# LP.net
KiCad netlist of a schematic drawn in Altium Designer
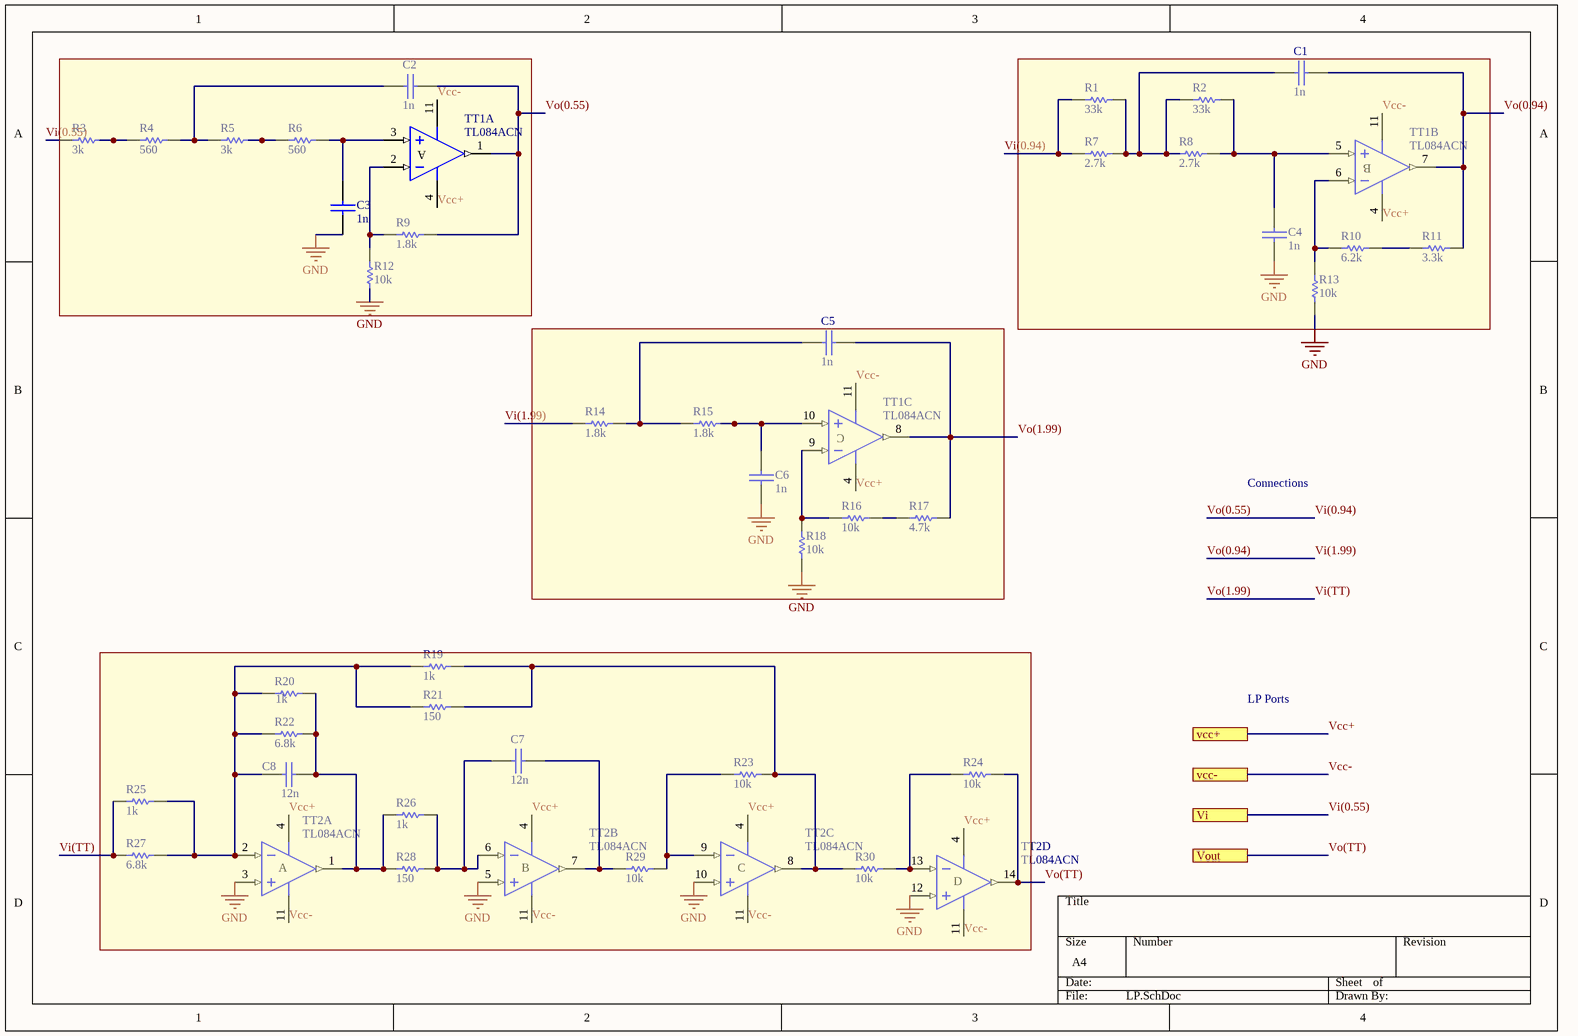
[diagram p0: LP.SchDoc]

(export (version "E")
  (design (tool "Eeschema 10.0.6"))
  (components
    (comp (ref "C1") (value "1n") (footprint "0805") (libsource (lib "LIBEBAL") (part "CAP")))
    (comp (ref "C2") (value "1n") (footprint "0805") (libsource (lib "LIBEBAL") (part "CAP")))
    (comp (ref "C3") (value "1n") (footprint "0805") (libsource (lib "LIBEBAL") (part "CAP")))
    (comp (ref "C4") (value "1n") (footprint "0805") (libsource (lib "LIBEBAL") (part "CAP")))
    (comp (ref "C5") (value "1n") (footprint "0805") (libsource (lib "LIBEBAL") (part "CAP")))
    (comp (ref "C6") (value "1n") (footprint "0805") (libsource (lib "LIBEBAL") (part "CAP")))
    (comp (ref "C7") (value "12n") (footprint "0805") (libsource (lib "LIBEBAL") (part "CAP")))
    (comp (ref "C8") (value "12n") (footprint "0805") (libsource (lib "LIBEBAL") (part "CAP")))
    (comp (ref "R1") (value "33k") (footprint "0805") (libsource (lib "LIBEBAL") (part "RES")))
    (comp (ref "R2") (value "33k") (footprint "0805") (libsource (lib "LIBEBAL") (part "RES")))
    (comp (ref "R3") (value "3k") (footprint "0805") (libsource (lib "LIBEBAL") (part "RES")))
    (comp (ref "R4") (value "560") (footprint "0805") (libsource (lib "LIBEBAL") (part "RES")))
    (comp (ref "R5") (value "3k") (footprint "0805") (libsource (lib "LIBEBAL") (part "RES")))
    (comp (ref "R6") (value "560") (footprint "0805") (libsource (lib "LIBEBAL") (part "RES")))
    (comp (ref "R7") (value "2.7k") (footprint "0805") (libsource (lib "LIBEBAL") (part "RES")))
    (comp (ref "R8") (value "2.7k") (footprint "0805") (libsource (lib "LIBEBAL") (part "RES")))
    (comp (ref "R9") (value "1.8k") (footprint "0805") (libsource (lib "LIBEBAL") (part "RES")))
    (comp (ref "R10") (value "6.2k") (footprint "0805") (libsource (lib "LIBEBAL") (part "RES")))
    (comp (ref "R11") (value "3.3k") (footprint "0805") (libsource (lib "LIBEBAL") (part "RES")))
    (comp (ref "R12") (value "10k") (footprint "0805") (libsource (lib "LIBEBAL") (part "RES")))
    (comp (ref "R13") (value "10k") (footprint "0805") (libsource (lib "LIBEBAL") (part "RES")))
    (comp (ref "R14") (value "1.8k") (footprint "0805") (libsource (lib "LIBEBAL") (part "RES")))
    (comp (ref "R15") (value "1.8k") (footprint "0805") (libsource (lib "LIBEBAL") (part "RES")))
    (comp (ref "R16") (value "10k") (footprint "0805") (libsource (lib "LIBEBAL") (part "RES")))
    (comp (ref "R17") (value "4.7k") (footprint "0805") (libsource (lib "LIBEBAL") (part "RES")))
    (comp (ref "R18") (value "10k") (footprint "0805") (libsource (lib "LIBEBAL") (part "RES")))
    (comp (ref "R19") (value "1k") (footprint "0805") (libsource (lib "LIBEBAL") (part "RES")))
    (comp (ref "R20") (value "1k") (footprint "0805") (libsource (lib "LIBEBAL") (part "RES")))
    (comp (ref "R21") (value "150") (footprint "0805") (libsource (lib "LIBEBAL") (part "RES")))
    (comp (ref "R22") (value "6.8k") (footprint "0805") (libsource (lib "LIBEBAL") (part "RES")))
    (comp (ref "R23") (value "10k") (footprint "0805") (libsource (lib "LIBEBAL") (part "RES")))
    (comp (ref "R24") (value "10k") (footprint "0805") (libsource (lib "LIBEBAL") (part "RES")))
    (comp (ref "R25") (value "1k") (footprint "0805") (libsource (lib "LIBEBAL") (part "RES")))
    (comp (ref "R26") (value "1k") (footprint "0805") (libsource (lib "LIBEBAL") (part "RES")))
    (comp (ref "R27") (value "6.8k") (footprint "0805") (libsource (lib "LIBEBAL") (part "RES")))
    (comp (ref "R28") (value "150") (footprint "0805") (libsource (lib "LIBEBAL") (part "RES")))
    (comp (ref "R29") (value "10k") (footprint "0805") (libsource (lib "LIBEBAL") (part "RES")))
    (comp (ref "R30") (value "10k") (footprint "0805") (libsource (lib "LIBEBAL") (part "RES")))
    (comp (ref "TT1")
      (value "TL084ACN")
      (footprint "DIP14")
      (description "General-Purpose J-FET Quad Operational Amplifier")
      (fields (field (name "PUBLISHER") "Altium Limited"))
      (libsource (lib "TI Amplifiers and Linear Operational Amplifier General Purpose") (part "TL084ACN"))
    )
    (comp (ref "TT2")
      (value "TL084ACN")
      (footprint "DIP14")
      (description "General-Purpose J-FET Quad Operational Amplifier")
      (fields (field (name "PUBLISHER") "Altium Limited"))
      (libsource (lib "TI Amplifiers and Linear Operational Amplifier General Purpose") (part "TL084ACN"))
    )
  )
  (nets
    (net (code "1") (name "/Vcc+") (class "Default")
      (node (ref "TT1") (pin "4") (pinfunction "V+_4") (pintype "power_in"))
      (node (ref "TT2") (pin "4") (pinfunction "V+_4") (pintype "power_in"))
    )
    (net (code "2") (name "/Vcc-") (class "Default")
      (node (ref "TT1") (pin "11") (pinfunction "V-_11") (pintype "power_in"))
      (node (ref "TT2") (pin "11") (pinfunction "V-_11") (pintype "power_in"))
    )
    (net (code "3") (name "/Vi(0.55)") (class "Default")
      (node (ref "R3") (pin "1") (pinfunction "1_1") (pintype "passive"))
    )
    (net (code "4") (name "/Vi(0.94)") (class "Default")
      (node (ref "C2") (pin "2") (pinfunction "2_2") (pintype "passive"))
      (node (ref "R1") (pin "1") (pinfunction "1_1") (pintype "passive"))
      (node (ref "R7") (pin "1") (pinfunction "1_1") (pintype "passive"))
      (node (ref "R9") (pin "1") (pinfunction "1_1") (pintype "passive"))
      (node (ref "TT1") (pin "1") (pinfunction "OUT_1") (pintype "output"))
    )
    (net (code "5") (name "/Vi(1.99)") (class "Default")
      (node (ref "C1") (pin "2") (pinfunction "2_2") (pintype "passive"))
      (node (ref "R11") (pin "2") (pinfunction "2_2") (pintype "passive"))
      (node (ref "R14") (pin "1") (pinfunction "1_1") (pintype "passive"))
      (node (ref "TT1") (pin "7") (pinfunction "OUT_7") (pintype "output"))
    )
    (net (code "6") (name "/Vi(TT)") (class "Default")
      (node (ref "C5") (pin "2") (pinfunction "2_2") (pintype "passive"))
      (node (ref "R17") (pin "1") (pinfunction "1_1") (pintype "passive"))
      (node (ref "R25") (pin "1") (pinfunction "1_1") (pintype "passive"))
      (node (ref "R27") (pin "1") (pinfunction "1_1") (pintype "passive"))
      (node (ref "TT1") (pin "8") (pinfunction "OUT_8") (pintype "output"))
    )
    (net (code "7") (name "/Vo(TT)") (class "Default")
      (node (ref "R24") (pin "2") (pinfunction "2_2") (pintype "passive"))
      (node (ref "TT2") (pin "14") (pinfunction "OUT_14") (pintype "output"))
    )
    (net (code "8") (name "GND") (class "Default")
      (node (ref "C3") (pin "1") (pinfunction "1_1") (pintype "passive"))
      (node (ref "C4") (pin "1") (pinfunction "1_1") (pintype "passive"))
      (node (ref "C6") (pin "1") (pinfunction "1_1") (pintype "passive"))
      (node (ref "R12") (pin "1") (pinfunction "1_1") (pintype "passive"))
      (node (ref "R13") (pin "1") (pinfunction "1_1") (pintype "passive"))
      (node (ref "R18") (pin "1") (pinfunction "1_1") (pintype "passive"))
      (node (ref "TT2") (pin "10") (pinfunction "IN+_10") (pintype "input"))
      (node (ref "TT2") (pin "12") (pinfunction "IN+_12") (pintype "input"))
      (node (ref "TT2") (pin "3") (pinfunction "IN+_3") (pintype "input"))
      (node (ref "TT2") (pin "5") (pinfunction "IN+_5") (pintype "input"))
    )
    (net (code "9") (name "Net-(C1-Pad1)") (class "Default")
      (node (ref "C1") (pin "1") (pinfunction "1_1") (pintype "passive"))
      (node (ref "R1") (pin "2") (pinfunction "2_2") (pintype "passive"))
      (node (ref "R2") (pin "1") (pinfunction "1_1") (pintype "passive"))
      (node (ref "R7") (pin "2") (pinfunction "2_2") (pintype "passive"))
      (node (ref "R8") (pin "1") (pinfunction "1_1") (pintype "passive"))
    )
    (net (code "10") (name "Net-(C2-Pad1)") (class "Default")
      (node (ref "C2") (pin "1") (pinfunction "1_1") (pintype "passive"))
      (node (ref "R4") (pin "2") (pinfunction "2_2") (pintype "passive"))
      (node (ref "R5") (pin "1") (pinfunction "1_1") (pintype "passive"))
    )
    (net (code "11") (name "Net-(C5-Pad1)") (class "Default")
      (node (ref "C5") (pin "1") (pinfunction "1_1") (pintype "passive"))
      (node (ref "R14") (pin "2") (pinfunction "2_2") (pintype "passive"))
      (node (ref "R15") (pin "1") (pinfunction "1_1") (pintype "passive"))
    )
    (net (code "12") (name "Net-(R3-Pad2)") (class "Default")
      (node (ref "R3") (pin "2") (pinfunction "2_2") (pintype "passive"))
      (node (ref "R4") (pin "1") (pinfunction "1_1") (pintype "passive"))
    )
    (net (code "13") (name "Net-(R5-Pad2)") (class "Default")
      (node (ref "R5") (pin "2") (pinfunction "2_2") (pintype "passive"))
      (node (ref "R6") (pin "1") (pinfunction "1_1") (pintype "passive"))
    )
    (net (code "14") (name "Net-(R10-Pad1)") (class "Default")
      (node (ref "R10") (pin "1") (pinfunction "1_1") (pintype "passive"))
      (node (ref "R11") (pin "1") (pinfunction "1_1") (pintype "passive"))
    )
    (net (code "15") (name "Net-(R16-Pad1)") (class "Default")
      (node (ref "R16") (pin "1") (pinfunction "1_1") (pintype "passive"))
      (node (ref "R17") (pin "2") (pinfunction "2_2") (pintype "passive"))
    )
    (net (code "16") (name "Net-(TT1A-IN+)") (class "Default")
      (node (ref "C3") (pin "2") (pinfunction "2_2") (pintype "passive"))
      (node (ref "R6") (pin "2") (pinfunction "2_2") (pintype "passive"))
      (node (ref "TT1") (pin "3") (pinfunction "IN+_3") (pintype "input"))
    )
    (net (code "17") (name "Net-(TT1A-IN-)") (class "Default")
      (node (ref "R12") (pin "2") (pinfunction "2_2") (pintype "passive"))
      (node (ref "R9") (pin "2") (pinfunction "2_2") (pintype "passive"))
      (node (ref "TT1") (pin "2") (pinfunction "IN-_2") (pintype "input"))
    )
    (net (code "18") (name "Net-(TT1B-IN+)") (class "Default")
      (node (ref "C4") (pin "2") (pinfunction "2_2") (pintype "passive"))
      (node (ref "R2") (pin "2") (pinfunction "2_2") (pintype "passive"))
      (node (ref "R8") (pin "2") (pinfunction "2_2") (pintype "passive"))
      (node (ref "TT1") (pin "5") (pinfunction "IN+_5") (pintype "input"))
    )
    (net (code "19") (name "Net-(TT1B-IN-)") (class "Default")
      (node (ref "R10") (pin "2") (pinfunction "2_2") (pintype "passive"))
      (node (ref "R13") (pin "2") (pinfunction "2_2") (pintype "passive"))
      (node (ref "TT1") (pin "6") (pinfunction "IN-_6") (pintype "input"))
    )
    (net (code "20") (name "Net-(TT1C-IN+)") (class "Default")
      (node (ref "C6") (pin "2") (pinfunction "2_2") (pintype "passive"))
      (node (ref "R15") (pin "2") (pinfunction "2_2") (pintype "passive"))
      (node (ref "TT1") (pin "10") (pinfunction "IN+_10") (pintype "input"))
    )
    (net (code "21") (name "Net-(TT1C-IN-)") (class "Default")
      (node (ref "R16") (pin "2") (pinfunction "2_2") (pintype "passive"))
      (node (ref "R18") (pin "2") (pinfunction "2_2") (pintype "passive"))
      (node (ref "TT1") (pin "9") (pinfunction "IN-_9") (pintype "input"))
    )
    (net (code "22") (name "Net-(TT2A-IN-)") (class "Default")
      (node (ref "C8") (pin "1") (pinfunction "1_1") (pintype "passive"))
      (node (ref "R19") (pin "1") (pinfunction "1_1") (pintype "passive"))
      (node (ref "R20") (pin "1") (pinfunction "1_1") (pintype "passive"))
      (node (ref "R21") (pin "1") (pinfunction "1_1") (pintype "passive"))
      (node (ref "R22") (pin "1") (pinfunction "1_1") (pintype "passive"))
      (node (ref "R25") (pin "2") (pinfunction "2_2") (pintype "passive"))
      (node (ref "R27") (pin "2") (pinfunction "2_2") (pintype "passive"))
      (node (ref "TT2") (pin "2") (pinfunction "IN-_2") (pintype "input"))
    )
    (net (code "23") (name "Net-(TT2A-OUT)") (class "Default")
      (node (ref "C8") (pin "2") (pinfunction "2_2") (pintype "passive"))
      (node (ref "R20") (pin "2") (pinfunction "2_2") (pintype "passive"))
      (node (ref "R22") (pin "2") (pinfunction "2_2") (pintype "passive"))
      (node (ref "R26") (pin "1") (pinfunction "1_1") (pintype "passive"))
      (node (ref "R28") (pin "1") (pinfunction "1_1") (pintype "passive"))
      (node (ref "TT2") (pin "1") (pinfunction "OUT_1") (pintype "output"))
    )
    (net (code "24") (name "Net-(TT2B-IN-)") (class "Default")
      (node (ref "C7") (pin "1") (pinfunction "1_1") (pintype "passive"))
      (node (ref "R26") (pin "2") (pinfunction "2_2") (pintype "passive"))
      (node (ref "R28") (pin "2") (pinfunction "2_2") (pintype "passive"))
      (node (ref "TT2") (pin "6") (pinfunction "IN-_6") (pintype "input"))
    )
    (net (code "25") (name "Net-(TT2B-OUT)") (class "Default")
      (node (ref "C7") (pin "2") (pinfunction "2_2") (pintype "passive"))
      (node (ref "R29") (pin "1") (pinfunction "1_1") (pintype "passive"))
      (node (ref "TT2") (pin "7") (pinfunction "OUT_7") (pintype "output"))
    )
    (net (code "26") (name "Net-(TT2C-IN-)") (class "Default")
      (node (ref "R23") (pin "1") (pinfunction "1_1") (pintype "passive"))
      (node (ref "R29") (pin "2") (pinfunction "2_2") (pintype "passive"))
      (node (ref "TT2") (pin "9") (pinfunction "IN-_9") (pintype "input"))
    )
    (net (code "27") (name "Net-(TT2C-OUT)") (class "Default")
      (node (ref "R19") (pin "2") (pinfunction "2_2") (pintype "passive"))
      (node (ref "R21") (pin "2") (pinfunction "2_2") (pintype "passive"))
      (node (ref "R23") (pin "2") (pinfunction "2_2") (pintype "passive"))
      (node (ref "R30") (pin "1") (pinfunction "1_1") (pintype "passive"))
      (node (ref "TT2") (pin "8") (pinfunction "OUT_8") (pintype "output"))
    )
    (net (code "28") (name "Net-(TT2D-IN-)") (class "Default")
      (node (ref "R24") (pin "1") (pinfunction "1_1") (pintype "passive"))
      (node (ref "R30") (pin "2") (pinfunction "2_2") (pintype "passive"))
      (node (ref "TT2") (pin "13") (pinfunction "IN-_13") (pintype "input"))
    )
  )
)
